# IMU_Micro-F103.net
KiCad netlist of a schematic drawn in Altium Designer
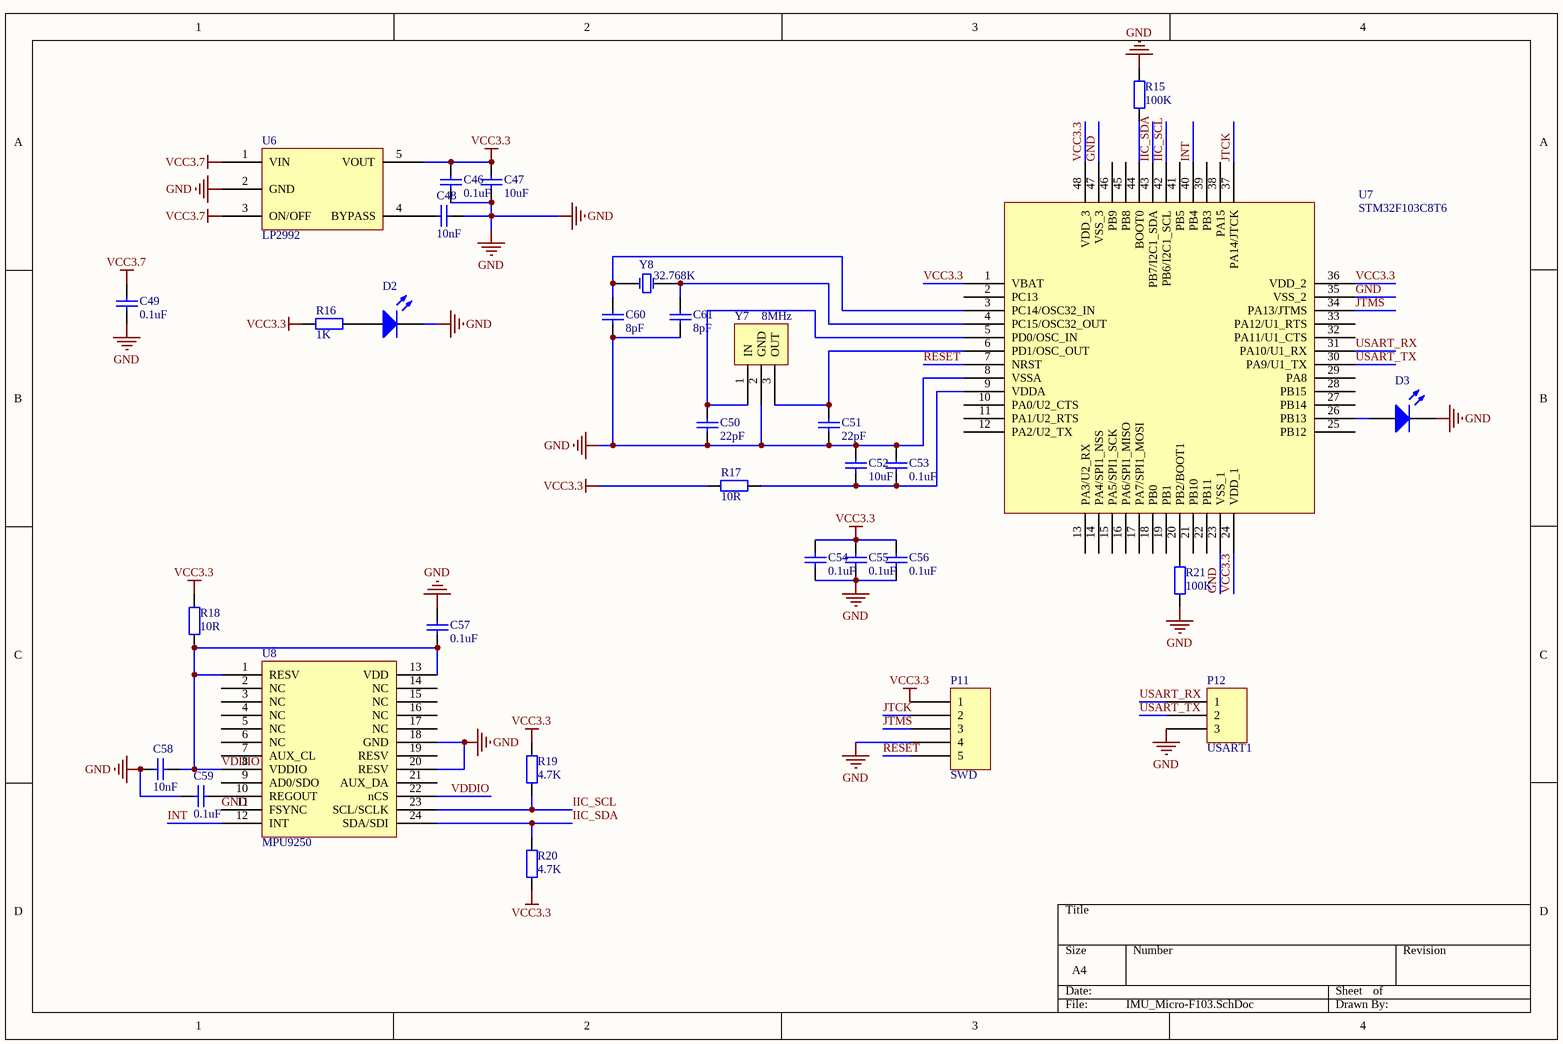
[diagram p0: IMU_Micro-F103.SchDoc]

(export (version "E")
  (design (tool "Eeschema 10.0.6"))
  (components
    (comp (ref "C46")
      (value "0.1uF")
      (footprint "C 0402_M")
      (description "Capacitor")
      (fields (field (name "PUBLISHER") "Altium Limited"))
      (libsource (lib "Miscellaneous Devices") (part "Cap"))
    )
    (comp (ref "C47")
      (value "10uF")
      (footprint "C 0402_M")
      (description "Capacitor")
      (fields (field (name "PUBLISHER") "Altium Limited"))
      (libsource (lib "Miscellaneous Devices") (part "Cap"))
    )
    (comp (ref "C48")
      (value "10nF")
      (footprint "C 0402_M")
      (description "Capacitor")
      (fields (field (name "PUBLISHER") "Altium Limited"))
      (libsource (lib "Miscellaneous Devices") (part "Cap"))
    )
    (comp (ref "C49")
      (value "0.1uF")
      (footprint "C 0402_M")
      (description "Capacitor")
      (fields (field (name "PUBLISHER") "Altium Limited"))
      (libsource (lib "Miscellaneous Devices") (part "Cap"))
    )
    (comp (ref "C50")
      (value "22pF")
      (footprint "C 0402_M")
      (description "Capacitor")
      (fields (field (name "PUBLISHER") "Altium Limited"))
      (libsource (lib "Miscellaneous Devices") (part "Cap"))
    )
    (comp (ref "C51")
      (value "22pF")
      (footprint "C 0402_M")
      (description "Capacitor")
      (fields (field (name "PUBLISHER") "Altium Limited"))
      (libsource (lib "Miscellaneous Devices") (part "Cap"))
    )
    (comp (ref "C52")
      (value "10uF")
      (footprint "C 0402_M")
      (description "Capacitor")
      (fields (field (name "PUBLISHER") "Altium Limited"))
      (libsource (lib "Miscellaneous Devices") (part "Cap"))
    )
    (comp (ref "C53")
      (value "0.1uF")
      (footprint "C 0402_M")
      (description "Capacitor")
      (fields (field (name "PUBLISHER") "Altium Limited"))
      (libsource (lib "Miscellaneous Devices") (part "Cap"))
    )
    (comp (ref "C54")
      (value "0.1uF")
      (footprint "C 0402_M")
      (description "Capacitor")
      (fields (field (name "PUBLISHER") "Altium Limited"))
      (libsource (lib "Miscellaneous Devices") (part "Cap"))
    )
    (comp (ref "C55")
      (value "0.1uF")
      (footprint "C 0402_M")
      (description "Capacitor")
      (fields (field (name "PUBLISHER") "Altium Limited"))
      (libsource (lib "Miscellaneous Devices") (part "Cap"))
    )
    (comp (ref "C56")
      (value "0.1uF")
      (footprint "C 0402_M")
      (description "Capacitor")
      (fields (field (name "PUBLISHER") "Altium Limited"))
      (libsource (lib "Miscellaneous Devices") (part "Cap"))
    )
    (comp (ref "C57")
      (value "0.1uF")
      (footprint "C 0402_M")
      (description "Capacitor")
      (fields (field (name "PUBLISHER") "Altium Limited"))
      (libsource (lib "Miscellaneous Devices") (part "Cap"))
    )
    (comp (ref "C58")
      (value "10nF")
      (footprint "C 0402_M")
      (description "Capacitor")
      (fields (field (name "PUBLISHER") "Altium Limited"))
      (libsource (lib "Miscellaneous Devices") (part "Cap"))
    )
    (comp (ref "C59")
      (value "0.1uF")
      (footprint "C 0402_M")
      (description "Capacitor")
      (fields (field (name "PUBLISHER") "Altium Limited"))
      (libsource (lib "Miscellaneous Devices") (part "Cap"))
    )
    (comp (ref "C60")
      (value "8pF")
      (footprint "C 0402_M")
      (description "Capacitor")
      (fields (field (name "PUBLISHER") "Altium Limited"))
      (libsource (lib "Miscellaneous Devices") (part "Cap"))
    )
    (comp (ref "C61")
      (value "8pF")
      (footprint "C 0402_M")
      (description "Capacitor")
      (fields (field (name "PUBLISHER") "Altium Limited"))
      (libsource (lib "Miscellaneous Devices") (part "Cap"))
    )
    (comp (ref "D2")
      (value "LED0")
      (footprint "R 0402_M")
      (description "Typical INFRARED GaAs LED")
      (fields (field (name "PUBLISHER") "Altium Limited"))
      (libsource (lib "Miscellaneous Devices") (part "LED0"))
    )
    (comp (ref "D3")
      (value "LED0")
      (footprint "R 0402_M")
      (description "Typical INFRARED GaAs LED")
      (fields (field (name "PUBLISHER") "Altium Limited"))
      (libsource (lib "Miscellaneous Devices") (part "LED0"))
    )
    (comp (ref "P11") (value "SWD") (footprint "HDR2.54-M-LI-5P") (libsource (lib "IMU主板") (part "SWD")))
    (comp (ref "P12") (value "USART1") (footprint "HDR2.54-M-LI-3P") (libsource (lib "IMU主板") (part "USART")))
    (comp (ref "R15")
      (value "100K")
      (footprint "R 0402_M")
      (description "Resistor")
      (fields (field (name "PUBLISHER") "Altium Limited"))
      (libsource (lib "Miscellaneous Devices") (part "Res2"))
    )
    (comp (ref "R16")
      (value "1K")
      (footprint "R 0402_M")
      (description "Resistor")
      (fields (field (name "PUBLISHER") "Altium Limited"))
      (libsource (lib "") (part "Res2_3"))
    )
    (comp (ref "R17")
      (value "10R")
      (footprint "R 0402_M")
      (description "Resistor")
      (fields (field (name "PUBLISHER") "Altium Limited"))
      (libsource (lib "") (part "Res2_1"))
    )
    (comp (ref "R18")
      (value "10R")
      (footprint "R 0402_M")
      (description "Resistor")
      (fields (field (name "PUBLISHER") "Altium Limited"))
      (libsource (lib "Miscellaneous Devices") (part "Res2"))
    )
    (comp (ref "R19")
      (value "4.7K")
      (footprint "R 0402_M")
      (description "Resistor")
      (fields (field (name "PUBLISHER") "Altium Limited"))
      (libsource (lib "") (part "Res2_2"))
    )
    (comp (ref "R20")
      (value "4.7K")
      (footprint "R 0402_M")
      (description "Resistor")
      (fields (field (name "PUBLISHER") "Altium Limited"))
      (libsource (lib "") (part "Res2_2"))
    )
    (comp (ref "R21")
      (value "100K")
      (footprint "R 0402_M")
      (description "Resistor")
      (fields (field (name "PUBLISHER") "Altium Limited"))
      (libsource (lib "Miscellaneous Devices") (part "Res2"))
    )
    (comp (ref "U6") (value "LP2992") (footprint "SOT23-5M") (libsource (lib "IMU主板") (part "LP2992")))
    (comp (ref "U7")
      (value "STM32F103C8T6")
      (footprint "LQFP48")
      (libsource (lib "IMU主板") (part "STM32F103CBT6"))
    )
    (comp (ref "U8") (value "MPU9250") (footprint "QFN24 3*3") (libsource (lib "IMU主板") (part "MPU9250")))
    (comp (ref "Y7") (value "8MHz") (footprint "SMD 3213-3P") (libsource (lib "IMU主板") (part "Y_3Pin")))
    (comp (ref "Y8")
      (value "32.768K")
      (footprint "SMD1610-2P")
      (description "Crystal Oscillator")
      (fields (field (name "PUBLISHER") "Altium Limited"))
      (libsource (lib "Miscellaneous Devices") (part "XTAL"))
    )
  )
  (nets
    (net (code "1") (name "/IIC_SCL") (class "Default")
      (node (ref "R19") (pin "1") (pinfunction "1_1") (pintype "passive"))
      (node (ref "U7") (pin "42") (pinfunction "PB6/I2C1_SCL_42") (pintype "passive"))
      (node (ref "U8") (pin "23") (pinfunction "SCL/SCLK_23") (pintype "passive"))
    )
    (net (code "2") (name "/IIC_SDA") (class "Default")
      (node (ref "R20") (pin "2") (pinfunction "2_2") (pintype "passive"))
      (node (ref "U7") (pin "43") (pinfunction "PB7/I2C1_SDA_43") (pintype "passive"))
      (node (ref "U8") (pin "24") (pinfunction "SDA/SDI_24") (pintype "passive"))
    )
    (net (code "3") (name "/INT") (class "Default")
      (node (ref "U7") (pin "40") (pinfunction "PB4_40") (pintype "passive"))
      (node (ref "U8") (pin "12") (pinfunction "INT_12") (pintype "passive"))
    )
    (net (code "4") (name "/JTCK") (class "Default")
      (node (ref "P11") (pin "2") (pinfunction "2_2") (pintype "passive"))
      (node (ref "U7") (pin "37") (pinfunction "PA14/JTCK_37") (pintype "passive"))
    )
    (net (code "5") (name "/JTMS") (class "Default")
      (node (ref "P11") (pin "3") (pinfunction "3_3") (pintype "passive"))
      (node (ref "U7") (pin "34") (pinfunction "PA13/JTMS_34") (pintype "passive"))
    )
    (net (code "6") (name "/RESET") (class "Default")
      (node (ref "P11") (pin "5") (pinfunction "5_5") (pintype "passive"))
      (node (ref "U7") (pin "7") (pinfunction "NRST_7") (pintype "passive"))
    )
    (net (code "7") (name "/USART_RX") (class "Default")
      (node (ref "P12") (pin "1") (pinfunction "1_1") (pintype "passive"))
      (node (ref "U7") (pin "31") (pinfunction "PA10/U1_RX_31") (pintype "passive"))
    )
    (net (code "8") (name "/USART_TX") (class "Default")
      (node (ref "P12") (pin "2") (pinfunction "2_2") (pintype "passive"))
      (node (ref "U7") (pin "30") (pinfunction "PA9/U1_TX_30") (pintype "passive"))
    )
    (net (code "9") (name "/VDDIO") (class "Default")
      (node (ref "C57") (pin "1") (pinfunction "1_1") (pintype "passive"))
      (node (ref "C58") (pin "2") (pinfunction "2_2") (pintype "passive"))
      (node (ref "R18") (pin "2") (pinfunction "2_2") (pintype "passive"))
      (node (ref "U8") (pin "1") (pinfunction "RESV_1") (pintype "passive"))
      (node (ref "U8") (pin "13") (pinfunction "VDD_13") (pintype "passive"))
      (node (ref "U8") (pin "22") (pinfunction "nCS_22") (pintype "passive"))
      (node (ref "U8") (pin "8") (pinfunction "VDDIO_8") (pintype "passive"))
    )
    (net (code "10") (name "GND") (class "Default")
      (node (ref "C46") (pin "2") (pinfunction "2_2") (pintype "passive"))
      (node (ref "C47") (pin "2") (pinfunction "2_2") (pintype "passive"))
      (node (ref "C48") (pin "2") (pinfunction "2_2") (pintype "passive"))
      (node (ref "C49") (pin "2") (pinfunction "2_2") (pintype "passive"))
      (node (ref "C50") (pin "2") (pinfunction "2_2") (pintype "passive"))
      (node (ref "C51") (pin "2") (pinfunction "2_2") (pintype "passive"))
      (node (ref "C52") (pin "1") (pinfunction "1_1") (pintype "passive"))
      (node (ref "C53") (pin "1") (pinfunction "1_1") (pintype "passive"))
      (node (ref "C54") (pin "2") (pinfunction "2_2") (pintype "passive"))
      (node (ref "C55") (pin "2") (pinfunction "2_2") (pintype "passive"))
      (node (ref "C56") (pin "2") (pinfunction "2_2") (pintype "passive"))
      (node (ref "C57") (pin "2") (pinfunction "2_2") (pintype "passive"))
      (node (ref "C58") (pin "1") (pinfunction "1_1") (pintype "passive"))
      (node (ref "C59") (pin "1") (pinfunction "1_1") (pintype "passive"))
      (node (ref "C60") (pin "2") (pinfunction "2_2") (pintype "passive"))
      (node (ref "C61") (pin "2") (pinfunction "2_2") (pintype "passive"))
      (node (ref "D2") (pin "2") (pinfunction "K_2") (pintype "passive"))
      (node (ref "D3") (pin "2") (pinfunction "K_2") (pintype "passive"))
      (node (ref "P11") (pin "4") (pinfunction "4_4") (pintype "passive"))
      (node (ref "P12") (pin "3") (pinfunction "3_3") (pintype "passive"))
      (node (ref "R15") (pin "1") (pinfunction "1_1") (pintype "passive"))
      (node (ref "R21") (pin "2") (pinfunction "2_2") (pintype "passive"))
      (node (ref "U6") (pin "2") (pinfunction "GND_2") (pintype "passive"))
      (node (ref "U7") (pin "23") (pinfunction "VSS_1_23") (pintype "passive"))
      (node (ref "U7") (pin "35") (pinfunction "VSS_2_35") (pintype "passive"))
      (node (ref "U7") (pin "47") (pinfunction "VSS_3_47") (pintype "passive"))
      (node (ref "U7") (pin "8") (pinfunction "VSSA_8") (pintype "passive"))
      (node (ref "U8") (pin "11") (pinfunction "FSYNC_11") (pintype "passive"))
      (node (ref "U8") (pin "18") (pinfunction "GND_18") (pintype "passive"))
      (node (ref "U8") (pin "20") (pinfunction "RESV_20") (pintype "passive"))
      (node (ref "Y7") (pin "2") (pinfunction "GND_2") (pintype "passive"))
    )
    (net (code "11") (name "Net-(D2-A)") (class "Default")
      (node (ref "D2") (pin "1") (pinfunction "A_1") (pintype "passive"))
      (node (ref "R16") (pin "1") (pinfunction "1_1") (pintype "passive"))
    )
    (net (code "12") (name "Net-(D3-A)") (class "Default")
      (node (ref "D3") (pin "1") (pinfunction "A_1") (pintype "passive"))
      (node (ref "U7") (pin "26") (pinfunction "PB13_26") (pintype "passive"))
    )
    (net (code "13") (name "Net-(U6-BYPASS)") (class "Default")
      (node (ref "C48") (pin "1") (pinfunction "1_1") (pintype "passive"))
      (node (ref "U6") (pin "4") (pinfunction "BYPASS_4") (pintype "passive"))
    )
    (net (code "14") (name "Net-(U7-BOOT0)") (class "Default")
      (node (ref "R15") (pin "2") (pinfunction "2_2") (pintype "passive"))
      (node (ref "U7") (pin "44") (pinfunction "BOOT0_44") (pintype "passive"))
    )
    (net (code "15") (name "Net-(U7-PB2{slash}BOOT1)") (class "Default")
      (node (ref "R21") (pin "1") (pinfunction "1_1") (pintype "passive"))
      (node (ref "U7") (pin "20") (pinfunction "PB2/BOOT1_20") (pintype "passive"))
    )
    (net (code "16") (name "Net-(U7-PC14{slash}OSC32_IN)") (class "Default")
      (node (ref "C60") (pin "1") (pinfunction "1_1") (pintype "passive"))
      (node (ref "U7") (pin "3") (pinfunction "PC14/OSC32_IN_3") (pintype "passive"))
      (node (ref "Y8") (pin "1") (pinfunction "OSC1_1") (pintype "passive"))
    )
    (net (code "17") (name "Net-(U7-PC15{slash}OSC32_OUT)") (class "Default")
      (node (ref "C61") (pin "1") (pinfunction "1_1") (pintype "passive"))
      (node (ref "U7") (pin "4") (pinfunction "PC15/OSC32_OUT_4") (pintype "passive"))
      (node (ref "Y8") (pin "2") (pinfunction "OSC2_2") (pintype "passive"))
    )
    (net (code "18") (name "Net-(U7-PD0{slash}OSC_IN)") (class "Default")
      (node (ref "C50") (pin "1") (pinfunction "1_1") (pintype "passive"))
      (node (ref "U7") (pin "5") (pinfunction "PD0/OSC_IN_5") (pintype "passive"))
      (node (ref "Y7") (pin "1") (pinfunction "IN_1") (pintype "passive"))
    )
    (net (code "19") (name "Net-(U7-PD1{slash}OSC_OUT)") (class "Default")
      (node (ref "C51") (pin "1") (pinfunction "1_1") (pintype "passive"))
      (node (ref "U7") (pin "6") (pinfunction "PD1/OSC_OUT_6") (pintype "passive"))
      (node (ref "Y7") (pin "3") (pinfunction "OUT_3") (pintype "passive"))
    )
    (net (code "20") (name "Net-(U7-VDDA)") (class "Default")
      (node (ref "C52") (pin "2") (pinfunction "2_2") (pintype "passive"))
      (node (ref "C53") (pin "2") (pinfunction "2_2") (pintype "passive"))
      (node (ref "R17") (pin "2") (pinfunction "2_2") (pintype "passive"))
      (node (ref "U7") (pin "9") (pinfunction "VDDA_9") (pintype "passive"))
    )
    (net (code "21") (name "Net-(U8-REGOUT)") (class "Default")
      (node (ref "C59") (pin "2") (pinfunction "2_2") (pintype "passive"))
      (node (ref "U8") (pin "10") (pinfunction "REGOUT_10") (pintype "passive"))
    )
    (net (code "22") (name "VCC3.3") (class "Default")
      (node (ref "C46") (pin "1") (pinfunction "1_1") (pintype "passive"))
      (node (ref "C47") (pin "1") (pinfunction "1_1") (pintype "passive"))
      (node (ref "C54") (pin "1") (pinfunction "1_1") (pintype "passive"))
      (node (ref "C55") (pin "1") (pinfunction "1_1") (pintype "passive"))
      (node (ref "C56") (pin "1") (pinfunction "1_1") (pintype "passive"))
      (node (ref "P11") (pin "1") (pinfunction "1_1") (pintype "passive"))
      (node (ref "R16") (pin "2") (pinfunction "2_2") (pintype "passive"))
      (node (ref "R17") (pin "1") (pinfunction "1_1") (pintype "passive"))
      (node (ref "R18") (pin "1") (pinfunction "1_1") (pintype "passive"))
      (node (ref "R19") (pin "2") (pinfunction "2_2") (pintype "passive"))
      (node (ref "R20") (pin "1") (pinfunction "1_1") (pintype "passive"))
      (node (ref "U6") (pin "5") (pinfunction "VOUT_5") (pintype "passive"))
      (node (ref "U7") (pin "1") (pinfunction "VBAT_1") (pintype "passive"))
      (node (ref "U7") (pin "24") (pinfunction "VDD_1_24") (pintype "passive"))
      (node (ref "U7") (pin "36") (pinfunction "VDD_2_36") (pintype "passive"))
      (node (ref "U7") (pin "48") (pinfunction "VDD_3_48") (pintype "passive"))
    )
    (net (code "23") (name "VCC3.7") (class "Default")
      (node (ref "C49") (pin "1") (pinfunction "1_1") (pintype "passive"))
      (node (ref "U6") (pin "1") (pinfunction "VIN_1") (pintype "passive"))
      (node (ref "U6") (pin "3") (pinfunction "ON/OFF_3") (pintype "passive"))
    )
    (net (code "24") (name "unconnected-(U7-PA0{slash}U2_CTS-Pad10)") (class "Default")
      (node (ref "U7") (pin "10") (pinfunction "PA0/U2_CTS_10") (pintype "passive"))
    )
    (net (code "25") (name "unconnected-(U7-PA1{slash}U2_RTS-Pad11)") (class "Default")
      (node (ref "U7") (pin "11") (pinfunction "PA1/U2_RTS_11") (pintype "passive"))
    )
    (net (code "26") (name "unconnected-(U7-PA2{slash}U2_TX-Pad12)") (class "Default")
      (node (ref "U7") (pin "12") (pinfunction "PA2/U2_TX_12") (pintype "passive"))
    )
    (net (code "27") (name "unconnected-(U7-PA3{slash}U2_RX-Pad13)") (class "Default")
      (node (ref "U7") (pin "13") (pinfunction "PA3/U2_RX_13") (pintype "passive"))
    )
    (net (code "28") (name "unconnected-(U7-PA4{slash}SPI1_NSS-Pad14)") (class "Default")
      (node (ref "U7") (pin "14") (pinfunction "PA4/SPI1_NSS_14") (pintype "passive"))
    )
    (net (code "29") (name "unconnected-(U7-PA5{slash}SPI1_SCK-Pad15)") (class "Default")
      (node (ref "U7") (pin "15") (pinfunction "PA5/SPI1_SCK_15") (pintype "passive"))
    )
    (net (code "30") (name "unconnected-(U7-PA6{slash}SPI1_MISO-Pad16)") (class "Default")
      (node (ref "U7") (pin "16") (pinfunction "PA6/SPI1_MISO_16") (pintype "passive"))
    )
    (net (code "31") (name "unconnected-(U7-PA7{slash}SPI1_MOSI-Pad17)") (class "Default")
      (node (ref "U7") (pin "17") (pinfunction "PA7/SPI1_MOSI_17") (pintype "passive"))
    )
    (net (code "32") (name "unconnected-(U7-PA8-Pad29)") (class "Default")
      (node (ref "U7") (pin "29") (pinfunction "PA8_29") (pintype "passive"))
    )
    (net (code "33") (name "unconnected-(U7-PA11{slash}U1_CTS-Pad32)") (class "Default")
      (node (ref "U7") (pin "32") (pinfunction "PA11/U1_CTS_32") (pintype "passive"))
    )
    (net (code "34") (name "unconnected-(U7-PA12{slash}U1_RTS-Pad33)") (class "Default")
      (node (ref "U7") (pin "33") (pinfunction "PA12/U1_RTS_33") (pintype "passive"))
    )
    (net (code "35") (name "unconnected-(U7-PA15-Pad38)") (class "Default")
      (node (ref "U7") (pin "38") (pinfunction "PA15_38") (pintype "passive"))
    )
    (net (code "36") (name "unconnected-(U7-PB0-Pad18)") (class "Default")
      (node (ref "U7") (pin "18") (pinfunction "PB0_18") (pintype "passive"))
    )
    (net (code "37") (name "unconnected-(U7-PB1-Pad19)") (class "Default")
      (node (ref "U7") (pin "19") (pinfunction "PB1_19") (pintype "passive"))
    )
    (net (code "38") (name "unconnected-(U7-PB3-Pad39)") (class "Default")
      (node (ref "U7") (pin "39") (pinfunction "PB3_39") (pintype "passive"))
    )
    (net (code "39") (name "unconnected-(U7-PB5-Pad41)") (class "Default")
      (node (ref "U7") (pin "41") (pinfunction "PB5_41") (pintype "passive"))
    )
    (net (code "40") (name "unconnected-(U7-PB8-Pad45)") (class "Default")
      (node (ref "U7") (pin "45") (pinfunction "PB8_45") (pintype "passive"))
    )
    (net (code "41") (name "unconnected-(U7-PB9-Pad46)") (class "Default")
      (node (ref "U7") (pin "46") (pinfunction "PB9_46") (pintype "passive"))
    )
    (net (code "42") (name "unconnected-(U7-PB10-Pad21)") (class "Default")
      (node (ref "U7") (pin "21") (pinfunction "PB10_21") (pintype "passive"))
    )
    (net (code "43") (name "unconnected-(U7-PB11-Pad22)") (class "Default")
      (node (ref "U7") (pin "22") (pinfunction "PB11_22") (pintype "passive"))
    )
    (net (code "44") (name "unconnected-(U7-PB12-Pad25)") (class "Default")
      (node (ref "U7") (pin "25") (pinfunction "PB12_25") (pintype "passive"))
    )
    (net (code "45") (name "unconnected-(U7-PB14-Pad27)") (class "Default")
      (node (ref "U7") (pin "27") (pinfunction "PB14_27") (pintype "passive"))
    )
    (net (code "46") (name "unconnected-(U7-PB15-Pad28)") (class "Default")
      (node (ref "U7") (pin "28") (pinfunction "PB15_28") (pintype "passive"))
    )
    (net (code "47") (name "unconnected-(U7-PC13-Pad2)") (class "Default")
      (node (ref "U7") (pin "2") (pinfunction "PC13_2") (pintype "passive"))
    )
    (net (code "48") (name "unconnected-(U8-AD0{slash}SDO-Pad9)") (class "Default")
      (node (ref "U8") (pin "9") (pinfunction "AD0/SDO_9") (pintype "passive"))
    )
    (net (code "49") (name "unconnected-(U8-AUX_CL-Pad7)") (class "Default")
      (node (ref "U8") (pin "7") (pinfunction "AUX_CL_7") (pintype "passive"))
    )
    (net (code "50") (name "unconnected-(U8-AUX_DA-Pad21)") (class "Default")
      (node (ref "U8") (pin "21") (pinfunction "AUX_DA_21") (pintype "passive"))
    )
    (net (code "51") (name "unconnected-(U8-NC-Pad2)") (class "Default")
      (node (ref "U8") (pin "2") (pinfunction "NC_2") (pintype "passive"))
    )
    (net (code "52") (name "unconnected-(U8-NC-Pad3)") (class "Default")
      (node (ref "U8") (pin "3") (pinfunction "NC_3") (pintype "passive"))
    )
    (net (code "53") (name "unconnected-(U8-NC-Pad4)") (class "Default")
      (node (ref "U8") (pin "4") (pinfunction "NC_4") (pintype "passive"))
    )
    (net (code "54") (name "unconnected-(U8-NC-Pad5)") (class "Default")
      (node (ref "U8") (pin "5") (pinfunction "NC_5") (pintype "passive"))
    )
    (net (code "55") (name "unconnected-(U8-NC-Pad6)") (class "Default")
      (node (ref "U8") (pin "6") (pinfunction "NC_6") (pintype "passive"))
    )
    (net (code "56") (name "unconnected-(U8-NC-Pad14)") (class "Default")
      (node (ref "U8") (pin "14") (pinfunction "NC_14") (pintype "passive"))
    )
    (net (code "57") (name "unconnected-(U8-NC-Pad15)") (class "Default")
      (node (ref "U8") (pin "15") (pinfunction "NC_15") (pintype "passive"))
    )
    (net (code "58") (name "unconnected-(U8-NC-Pad16)") (class "Default")
      (node (ref "U8") (pin "16") (pinfunction "NC_16") (pintype "passive"))
    )
    (net (code "59") (name "unconnected-(U8-NC-Pad17)") (class "Default")
      (node (ref "U8") (pin "17") (pinfunction "NC_17") (pintype "passive"))
    )
    (net (code "60") (name "unconnected-(U8-RESV-Pad19)") (class "Default")
      (node (ref "U8") (pin "19") (pinfunction "RESV_19") (pintype "passive"))
    )
  )
)
